# ESP32.net
KiCad netlist of a schematic drawn in Altium Designer
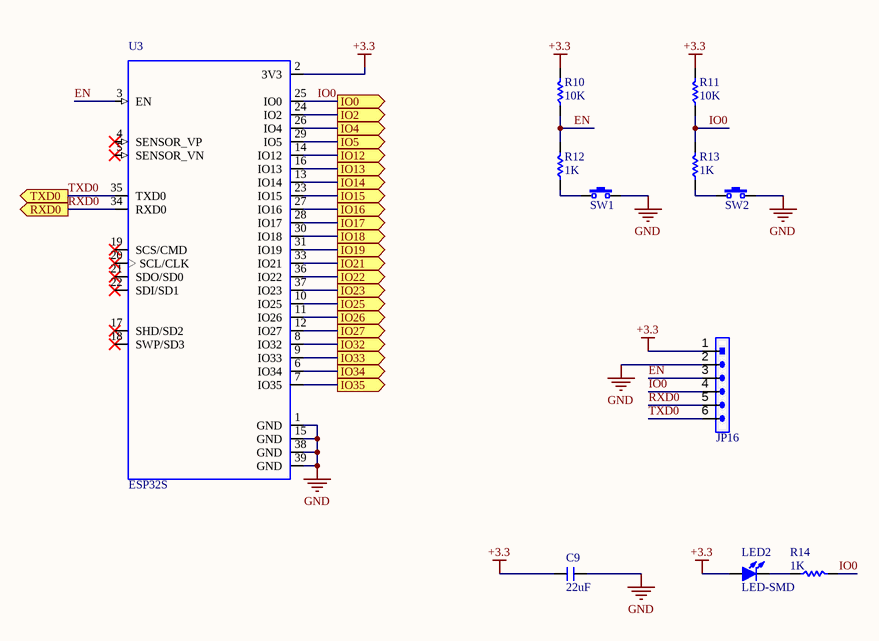
[diagram p0: ESP32.SchDoc]

(export (version "E")
  (design (tool "Eeschema 10.0.6"))
  (components
    (comp (ref "C9")
      (value "22uF")
      (footprint "C 0805")
      (description "Non-polar patch capacitor")
      (fields (field (name "版权归属") "源创客"))
      (libsource (lib "Passive (Resistor-Capacitor-Inductor-Veristor-Ferrite)") (part "C"))
    )
    (comp (ref "JP16")
      (value "HDR-1X6")
      (footprint "HDR-1X6")
      (description "6P Connector")
      (fields (field (name "版权归属") "源创客"))
      (libsource (lib "Connectors") (part "Header 6"))
    )
    (comp (ref "LED2")
      (value "LED-SMD")
      (footprint "LED 0805B")
      (description "Patch LED")
      (fields (field (name "版权归属") "源创客"))
      (libsource (lib "LED") (part "LED-SMD"))
    )
    (comp (ref "R10")
      (value "10K")
      (footprint "R 0805")
      (description "Chip resistor")
      (fields (field (name "版权归属") "源创客"))
      (libsource (lib "Passive (Resistor-Capacitor-Inductor-Veristor-Ferrite)") (part "R"))
    )
    (comp (ref "R11")
      (value "10K")
      (footprint "R 0805")
      (description "Chip resistor")
      (fields (field (name "版权归属") "源创客"))
      (libsource (lib "Passive (Resistor-Capacitor-Inductor-Veristor-Ferrite)") (part "R"))
    )
    (comp (ref "R12")
      (value "1K")
      (footprint "R 0805")
      (description "Chip resistor")
      (fields (field (name "版权归属") "源创客"))
      (libsource (lib "Passive (Resistor-Capacitor-Inductor-Veristor-Ferrite)") (part "R"))
    )
    (comp (ref "R13")
      (value "1K")
      (footprint "R 0805")
      (description "Chip resistor")
      (fields (field (name "版权归属") "源创客"))
      (libsource (lib "Passive (Resistor-Capacitor-Inductor-Veristor-Ferrite)") (part "R"))
    )
    (comp (ref "R14")
      (value "1K")
      (footprint "R 0805")
      (description "Chip resistor")
      (fields (field (name "版权归属") "源创客"))
      (libsource (lib "Passive (Resistor-Capacitor-Inductor-Veristor-Ferrite)") (part "R"))
    )
    (comp (ref "SW1")
      (value "3x6x5")
      (footprint "TSW SMD-3*6*2.5")
      (description "3x6 tact switch")
      (fields (field (name "版权归属") "源创客"))
      (libsource (lib "Button") (part "TSW 3x6"))
    )
    (comp (ref "SW2")
      (value "3x6x5")
      (footprint "TSW SMD-3*6*2.5")
      (description "3x6 tact switch")
      (fields (field (name "版权归属") "源创客"))
      (libsource (lib "Button") (part "TSW 3x6"))
    )
    (comp (ref "U3")
      (value "ESP32S")
      (footprint "ESP32S")
      (fields (field (name "MP") "ESP32-WROOM-32D") (field (name "MF") "Espressif Systems"))
      (libsource (lib "Espressif") (part "ESP32S"))
    )
  )
  (nets
    (net (code "1") (name "+3.3") (class "Default")
      (node (ref "C9") (pin "1") (pinfunction "1_1") (pintype "passive"))
      (node (ref "JP16") (pin "1") (pintype "passive"))
      (node (ref "LED2") (pin "1") (pinfunction "A_1") (pintype "passive"))
      (node (ref "R10") (pin "2") (pinfunction "2_2") (pintype "passive"))
      (node (ref "R11") (pin "2") (pinfunction "2_2") (pintype "passive"))
      (node (ref "U3") (pin "2") (pinfunction "3V3_2") (pintype "power_in"))
    )
    (net (code "2") (name "/EN") (class "Default")
      (node (ref "JP16") (pin "3") (pintype "passive"))
      (node (ref "R10") (pin "1") (pinfunction "1_1") (pintype "passive"))
      (node (ref "R12") (pin "2") (pinfunction "2_2") (pintype "passive"))
      (node (ref "U3") (pin "3") (pinfunction "EN_3") (pintype "input"))
    )
    (net (code "3") (name "/IO0") (class "Default")
      (node (ref "JP16") (pin "4") (pintype "passive"))
      (node (ref "R11") (pin "1") (pinfunction "1_1") (pintype "passive"))
      (node (ref "R13") (pin "2") (pinfunction "2_2") (pintype "passive"))
      (node (ref "R14") (pin "2") (pinfunction "2_2") (pintype "passive"))
      (node (ref "U3") (pin "25") (pinfunction "IO0_25") (pintype "bidirectional"))
    )
    (net (code "4") (name "/IO2") (class "Default")
      (node (ref "U3") (pin "24") (pinfunction "IO2_24") (pintype "bidirectional"))
    )
    (net (code "5") (name "/IO4") (class "Default")
      (node (ref "U3") (pin "26") (pinfunction "IO4_26") (pintype "bidirectional"))
    )
    (net (code "6") (name "/IO5") (class "Default")
      (node (ref "U3") (pin "29") (pinfunction "IO5_29") (pintype "bidirectional"))
    )
    (net (code "7") (name "/IO12") (class "Default")
      (node (ref "U3") (pin "14") (pinfunction "IO12_14") (pintype "bidirectional"))
    )
    (net (code "8") (name "/IO13") (class "Default")
      (node (ref "U3") (pin "16") (pinfunction "IO13_16") (pintype "bidirectional"))
    )
    (net (code "9") (name "/IO14") (class "Default")
      (node (ref "U3") (pin "13") (pinfunction "IO14_13") (pintype "bidirectional"))
    )
    (net (code "10") (name "/IO15") (class "Default")
      (node (ref "U3") (pin "23") (pinfunction "IO15_23") (pintype "bidirectional"))
    )
    (net (code "11") (name "/IO16") (class "Default")
      (node (ref "U3") (pin "27") (pinfunction "IO16_27") (pintype "bidirectional"))
    )
    (net (code "12") (name "/IO17") (class "Default")
      (node (ref "U3") (pin "28") (pinfunction "IO17_28") (pintype "bidirectional"))
    )
    (net (code "13") (name "/IO18") (class "Default")
      (node (ref "U3") (pin "30") (pinfunction "IO18_30") (pintype "bidirectional"))
    )
    (net (code "14") (name "/IO19") (class "Default")
      (node (ref "U3") (pin "31") (pinfunction "IO19_31") (pintype "bidirectional"))
    )
    (net (code "15") (name "/IO21") (class "Default")
      (node (ref "U3") (pin "33") (pinfunction "IO21_33") (pintype "bidirectional"))
    )
    (net (code "16") (name "/IO22") (class "Default")
      (node (ref "U3") (pin "36") (pinfunction "IO22_36") (pintype "bidirectional"))
    )
    (net (code "17") (name "/IO23") (class "Default")
      (node (ref "U3") (pin "37") (pinfunction "IO23_37") (pintype "bidirectional"))
    )
    (net (code "18") (name "/IO25") (class "Default")
      (node (ref "U3") (pin "10") (pinfunction "IO25_10") (pintype "bidirectional"))
    )
    (net (code "19") (name "/IO26") (class "Default")
      (node (ref "U3") (pin "11") (pinfunction "IO26_11") (pintype "bidirectional"))
    )
    (net (code "20") (name "/IO27") (class "Default")
      (node (ref "U3") (pin "12") (pinfunction "IO27_12") (pintype "bidirectional"))
    )
    (net (code "21") (name "/IO32") (class "Default")
      (node (ref "U3") (pin "8") (pinfunction "IO32_8") (pintype "bidirectional"))
    )
    (net (code "22") (name "/IO33") (class "Default")
      (node (ref "U3") (pin "9") (pinfunction "IO33_9") (pintype "bidirectional"))
    )
    (net (code "23") (name "/IO34") (class "Default")
      (node (ref "U3") (pin "6") (pinfunction "IO34_6") (pintype "bidirectional"))
    )
    (net (code "24") (name "/IO35") (class "Default")
      (node (ref "U3") (pin "7") (pinfunction "IO35_7") (pintype "bidirectional"))
    )
    (net (code "25") (name "/RXD0") (class "Default")
      (node (ref "JP16") (pin "5") (pintype "passive"))
      (node (ref "U3") (pin "34") (pinfunction "RXD0_34") (pintype "bidirectional"))
    )
    (net (code "26") (name "/TXD0") (class "Default")
      (node (ref "JP16") (pin "6") (pintype "passive"))
      (node (ref "U3") (pin "35") (pinfunction "TXD0_35") (pintype "bidirectional"))
    )
    (net (code "27") (name "GND") (class "Default")
      (node (ref "C9") (pin "2") (pinfunction "2_2") (pintype "passive"))
      (node (ref "JP16") (pin "2") (pintype "passive"))
      (node (ref "SW1") (pin "2") (pinfunction "2_2") (pintype "passive"))
      (node (ref "SW2") (pin "2") (pinfunction "2_2") (pintype "passive"))
      (node (ref "U3") (pin "1") (pinfunction "GND_1") (pintype "power_in"))
      (node (ref "U3") (pin "15") (pinfunction "GND_15") (pintype "power_in"))
      (node (ref "U3") (pin "38") (pinfunction "GND_38") (pintype "power_in"))
      (node (ref "U3") (pin "39") (pinfunction "GND_39") (pintype "power_in"))
    )
    (net (code "28") (name "Net-(LED2-K)") (class "Default")
      (node (ref "LED2") (pin "2") (pinfunction "K_2") (pintype "passive"))
      (node (ref "R14") (pin "1") (pinfunction "1_1") (pintype "passive"))
    )
    (net (code "29") (name "Net-(R12-Pad1)") (class "Default")
      (node (ref "R12") (pin "1") (pinfunction "1_1") (pintype "passive"))
      (node (ref "SW1") (pin "1") (pinfunction "1_1") (pintype "passive"))
    )
    (net (code "30") (name "Net-(R13-Pad1)") (class "Default")
      (node (ref "R13") (pin "1") (pinfunction "1_1") (pintype "passive"))
      (node (ref "SW2") (pin "1") (pinfunction "1_1") (pintype "passive"))
    )
    (net (code "31") (name "unconnected-(U3-SCL{slash}CLK-Pad20)") (class "Default")
      (node (ref "U3") (pin "20") (pinfunction "SCL/CLK_20") (pintype "bidirectional+no_connect"))
    )
    (net (code "32") (name "unconnected-(U3-SCS{slash}CMD-Pad19)") (class "Default")
      (node (ref "U3") (pin "19") (pinfunction "SCS/CMD_19") (pintype "bidirectional+no_connect"))
    )
    (net (code "33") (name "unconnected-(U3-SDI{slash}SD1-Pad22)") (class "Default")
      (node (ref "U3") (pin "22") (pinfunction "SDI/SD1_22") (pintype "bidirectional+no_connect"))
    )
    (net (code "34") (name "unconnected-(U3-SDO{slash}SD0-Pad21)") (class "Default")
      (node (ref "U3") (pin "21") (pinfunction "SDO/SD0_21") (pintype "bidirectional+no_connect"))
    )
    (net (code "35") (name "unconnected-(U3-SENSOR_VN-Pad5)") (class "Default")
      (node (ref "U3") (pin "5") (pinfunction "SENSOR_VN_5") (pintype "input+no_connect"))
    )
    (net (code "36") (name "unconnected-(U3-SENSOR_VP-Pad4)") (class "Default")
      (node (ref "U3") (pin "4") (pinfunction "SENSOR_VP_4") (pintype "input+no_connect"))
    )
    (net (code "37") (name "unconnected-(U3-SHD{slash}SD2-Pad17)") (class "Default")
      (node (ref "U3") (pin "17") (pinfunction "SHD/SD2_17") (pintype "bidirectional+no_connect"))
    )
    (net (code "38") (name "unconnected-(U3-SWP{slash}SD3-Pad18)") (class "Default")
      (node (ref "U3") (pin "18") (pinfunction "SWP/SD3_18") (pintype "bidirectional+no_connect"))
    )
  )
)
